# SensorBoard_v1.net
KiCad netlist of a schematic drawn in Altium Designer
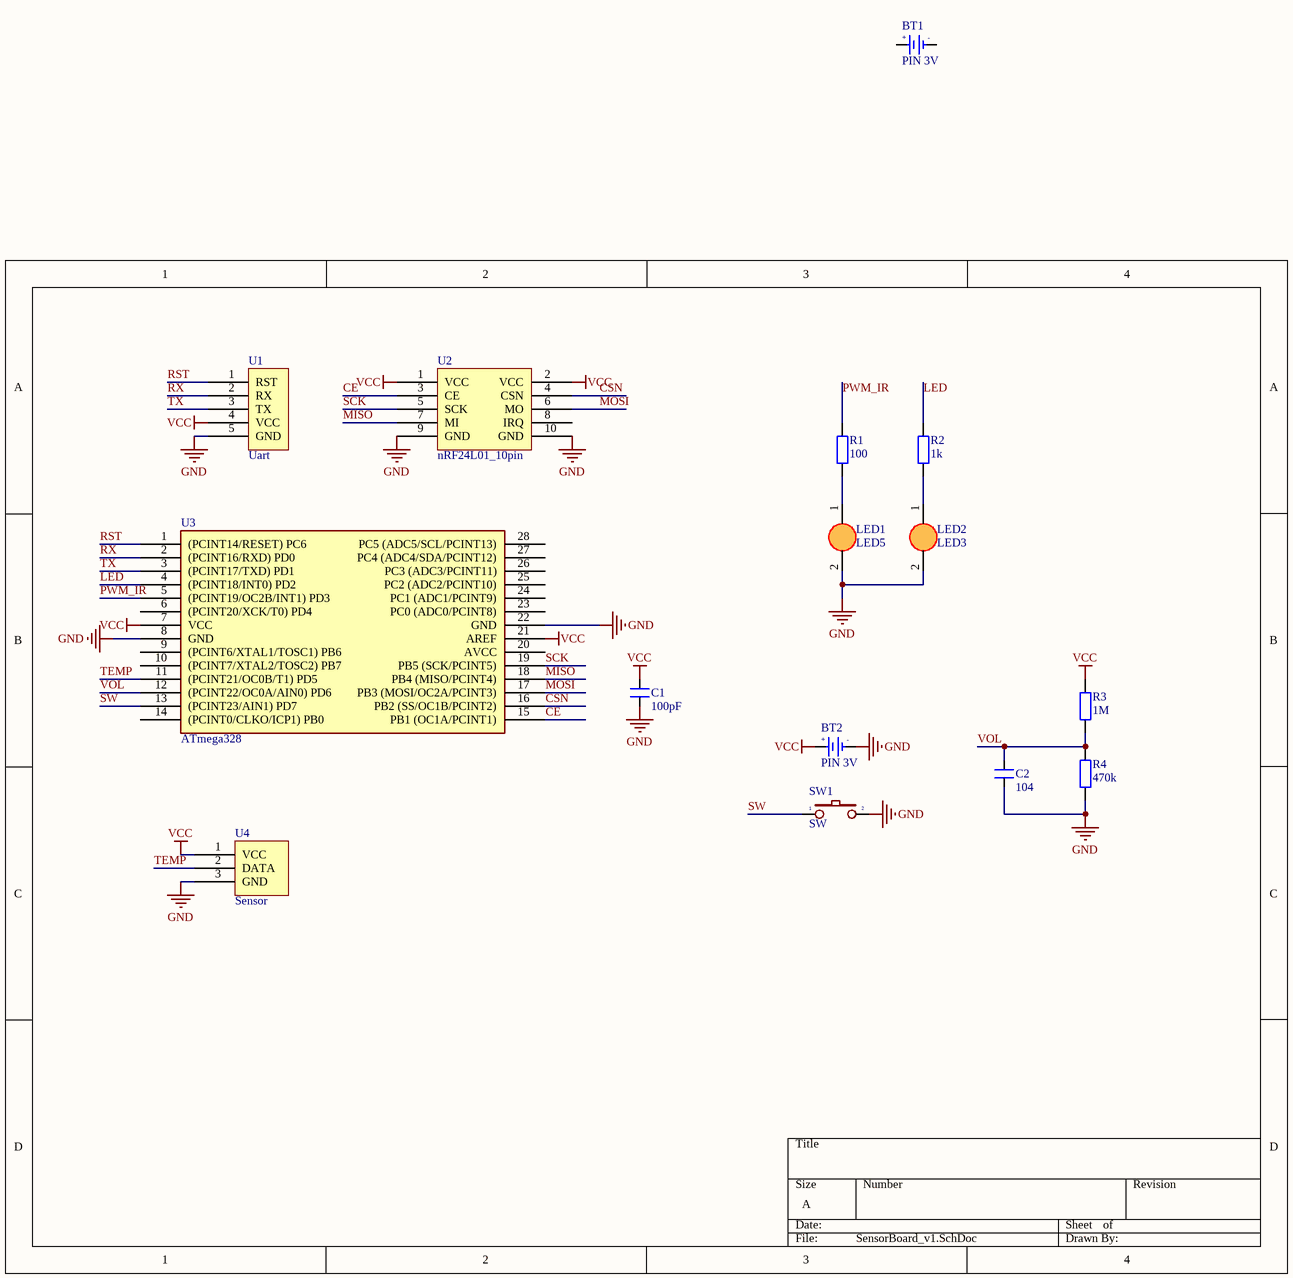
[diagram p0: SensorBoard_v1.SchDoc]

(export (version "E")
  (design (tool "Eeschema 10.0.6"))
  (components
    (comp (ref "BT1")
      (value "PIN 3V")
      (footprint "PIN3V")
      (description "Battery 3VDC")
      (libsource (lib "syhaunguyen") (part "PIN 3V"))
    )
    (comp (ref "BT2")
      (value "PIN 3V")
      (footprint "PIN3V")
      (description "Battery 3VDC")
      (libsource (lib "syhaunguyen") (part "PIN 3V"))
    )
    (comp (ref "C1")
      (value "100pF")
      (footprint "CN1")
      (description "Cap np  1pF - 472pF")
      (libsource (lib "syhaunguyen") (part "CN1"))
    )
    (comp (ref "C2")
      (value "104")
      (footprint "CN1.5")
      (description "Cap np 682pF => 104pF")
      (libsource (lib "syhaunguyen") (part "CN1.5"))
    )
    (comp (ref "LED1")
      (value "LED5")
      (footprint "LED5MM")
      (description "LED 5mm")
      (libsource (lib "myLibs") (part "LED 5mm"))
    )
    (comp (ref "LED2")
      (value "LED3")
      (footprint "LED3mm")
      (description "LED 3mm")
      (libsource (lib "myLibs") (part "LED 3mm"))
    )
    (comp (ref "R1")
      (value "100")
      (footprint "R1/4W")
      (description "Resistor 1/4W")
      (libsource (lib "myLibs") (part "R1/4W"))
    )
    (comp (ref "R2")
      (value "1k")
      (footprint "R1/4W")
      (description "Resistor 1/4W")
      (libsource (lib "myLibs") (part "R1/4W"))
    )
    (comp (ref "R3")
      (value "1M")
      (footprint "R1/4W")
      (description "Resistor 1/4W")
      (libsource (lib "myLibs") (part "R1/4W"))
    )
    (comp (ref "R4")
      (value "470k")
      (footprint "R1/4W")
      (description "Resistor 1/4W")
      (libsource (lib "myLibs") (part "R1/4W"))
    )
    (comp (ref "SW1")
      (value "SW")
      (footprint "SW2")
      (description "Switch button 2 pin")
      (libsource (lib "syhaunguyen") (part "SW2"))
    )
    (comp (ref "U1") (value "Uart") (footprint "CONG NAP") (libsource (lib "myLibs") (part "CONG NAP")))
    (comp (ref "U2")
      (value "nRF24L01_10pin")
      (footprint "NRF24L01_10PIN")
      (libsource (lib "myLibs") (part "nRF24L01_10pin"))
    )
    (comp (ref "U3") (value "ATmega328") (footprint "DIP28") (libsource (lib "myLibs") (part "ATmega328")))
    (comp (ref "U4")
      (value "Sensor")
      (footprint "TEMPSENSOR")
      (libsource (lib "myLibs") (part "Temp Sensor"))
    )
  )
  (nets
    (net (code "1") (name "/CE") (class "Default")
      (node (ref "U2") (pin "3") (pinfunction "CE_3") (pintype "passive"))
      (node (ref "U3") (pin "15") (pinfunction "PB1_(OC1A/PCINT1)_15") (pintype "passive"))
    )
    (net (code "2") (name "/CSN") (class "Default")
      (node (ref "U2") (pin "4") (pinfunction "CSN_4") (pintype "passive"))
      (node (ref "U3") (pin "16") (pinfunction "PB2_(SS/OC1B/PCINT2)_16") (pintype "passive"))
    )
    (net (code "3") (name "/LED") (class "Default")
      (node (ref "R2") (pin "1") (pinfunction "1_1") (pintype "passive"))
      (node (ref "U3") (pin "4") (pinfunction "(PCINT18/INT0)_PD2_4") (pintype "passive"))
    )
    (net (code "4") (name "/MISO") (class "Default")
      (node (ref "U2") (pin "7") (pinfunction "MI_7") (pintype "passive"))
      (node (ref "U3") (pin "18") (pinfunction "PB4_(MISO/PCINT4)_18") (pintype "passive"))
    )
    (net (code "5") (name "/MOSI") (class "Default")
      (node (ref "U2") (pin "6") (pinfunction "MO_6") (pintype "passive"))
      (node (ref "U3") (pin "17") (pinfunction "PB3_(MOSI/OC2A/PCINT3)_17") (pintype "passive"))
    )
    (net (code "6") (name "/PWM_IR") (class "Default")
      (node (ref "R1") (pin "2") (pinfunction "2_2") (pintype "passive"))
      (node (ref "U3") (pin "5") (pinfunction "(PCINT19/OC2B/INT1)_PD3_5") (pintype "passive"))
    )
    (net (code "7") (name "/RST") (class "Default")
      (node (ref "U1") (pin "1") (pinfunction "RST_1") (pintype "passive"))
      (node (ref "U3") (pin "1") (pinfunction "(PCINT14/RESET)_PC6_1") (pintype "passive"))
    )
    (net (code "8") (name "/RX") (class "Default")
      (node (ref "U1") (pin "2") (pinfunction "RX_2") (pintype "passive"))
      (node (ref "U3") (pin "2") (pinfunction "(PCINT16/RXD)_PD0_2") (pintype "passive"))
    )
    (net (code "9") (name "/SCK") (class "Default")
      (node (ref "U2") (pin "5") (pinfunction "SCK_5") (pintype "passive"))
      (node (ref "U3") (pin "19") (pinfunction "PB5_(SCK/PCINT5)_19") (pintype "passive"))
    )
    (net (code "10") (name "/SW") (class "Default")
      (node (ref "SW1") (pin "1") (pinfunction "1_1") (pintype "passive"))
      (node (ref "U3") (pin "13") (pinfunction "(PCINT23/AIN1)_PD7_13") (pintype "passive"))
    )
    (net (code "11") (name "/TEMP") (class "Default")
      (node (ref "U3") (pin "11") (pinfunction "(PCINT21/OC0B/T1)_PD5_11") (pintype "passive"))
      (node (ref "U4") (pin "2") (pinfunction "DATA_2") (pintype "passive"))
    )
    (net (code "12") (name "/TX") (class "Default")
      (node (ref "U1") (pin "3") (pinfunction "TX_3") (pintype "passive"))
      (node (ref "U3") (pin "3") (pinfunction "(PCINT17/TXD)_PD1_3") (pintype "passive"))
    )
    (net (code "13") (name "/VOL") (class "Default")
      (node (ref "C2") (pin "1") (pinfunction "1_1") (pintype "passive"))
      (node (ref "R3") (pin "2") (pinfunction "2_2") (pintype "passive"))
      (node (ref "R4") (pin "1") (pinfunction "1_1") (pintype "passive"))
      (node (ref "U3") (pin "12") (pinfunction "(PCINT22/OC0A/AIN0)_PD6_12") (pintype "passive"))
    )
    (net (code "14") (name "GND") (class "Default")
      (node (ref "BT2") (pin "2") (pinfunction "GND_2") (pintype "passive"))
      (node (ref "C1") (pin "2") (pinfunction "2_2") (pintype "passive"))
      (node (ref "C2") (pin "2") (pinfunction "2_2") (pintype "passive"))
      (node (ref "LED1") (pin "2") (pinfunction "K_2") (pintype "passive"))
      (node (ref "LED2") (pin "2") (pinfunction "K_2") (pintype "passive"))
      (node (ref "R4") (pin "2") (pinfunction "2_2") (pintype "passive"))
      (node (ref "SW1") (pin "2") (pinfunction "2_2") (pintype "passive"))
      (node (ref "U1") (pin "5") (pinfunction "GND_5") (pintype "passive"))
      (node (ref "U2") (pin "10") (pinfunction "GND_10") (pintype "passive"))
      (node (ref "U2") (pin "9") (pinfunction "GND_9") (pintype "passive"))
      (node (ref "U3") (pin "22") (pinfunction "GND_22") (pintype "passive"))
      (node (ref "U3") (pin "8") (pinfunction "GND_8") (pintype "passive"))
      (node (ref "U4") (pin "3") (pinfunction "GND_3") (pintype "passive"))
    )
    (net (code "15") (name "Net-(LED1-A)") (class "Default")
      (node (ref "LED1") (pin "1") (pinfunction "A_1") (pintype "passive"))
      (node (ref "R1") (pin "1") (pinfunction "1_1") (pintype "passive"))
    )
    (net (code "16") (name "Net-(LED2-A)") (class "Default")
      (node (ref "LED2") (pin "1") (pinfunction "A_1") (pintype "passive"))
      (node (ref "R2") (pin "2") (pinfunction "2_2") (pintype "passive"))
    )
    (net (code "17") (name "VCC") (class "Default")
      (node (ref "BT2") (pin "1") (pinfunction "+3V_1") (pintype "passive"))
      (node (ref "C1") (pin "1") (pinfunction "1_1") (pintype "passive"))
      (node (ref "R3") (pin "1") (pinfunction "1_1") (pintype "passive"))
      (node (ref "U1") (pin "4") (pinfunction "VCC_4") (pintype "passive"))
      (node (ref "U2") (pin "1") (pinfunction "VCC_1") (pintype "passive"))
      (node (ref "U2") (pin "2") (pinfunction "VCC_2") (pintype "passive"))
      (node (ref "U3") (pin "21") (pinfunction "AREF_21") (pintype "passive"))
      (node (ref "U3") (pin "7") (pinfunction "VCC_7") (pintype "passive"))
      (node (ref "U4") (pin "1") (pinfunction "VCC_1") (pintype "passive"))
    )
    (net (code "18") (name "unconnected-(BT1-+3V-Pad1)") (class "Default")
      (node (ref "BT1") (pin "1") (pinfunction "+3V_1") (pintype "passive"))
    )
    (net (code "19") (name "unconnected-(BT1-GND-Pad2)") (class "Default")
      (node (ref "BT1") (pin "2") (pinfunction "GND_2") (pintype "passive"))
    )
    (net (code "20") (name "unconnected-(U2-IRQ-Pad8)") (class "Default")
      (node (ref "U2") (pin "8") (pinfunction "IRQ_8") (pintype "passive"))
    )
    (net (code "21") (name "unconnected-(U3-(PCINT0{slash}CLKO{slash}ICP1)_PB0-Pad14)") (class "Default")
      (node (ref "U3") (pin "14") (pinfunction "(PCINT0/CLKO/ICP1)_PB0_14") (pintype "passive"))
    )
    (net (code "22") (name "unconnected-(U3-(PCINT6{slash}XTAL1{slash}TOSC1)_PB6-Pad9)") (class "Default")
      (node (ref "U3") (pin "9") (pinfunction "(PCINT6/XTAL1/TOSC1)_PB6_9") (pintype "passive"))
    )
    (net (code "23") (name "unconnected-(U3-(PCINT7{slash}XTAL2{slash}TOSC2)_PB7-Pad10)") (class "Default")
      (node (ref "U3") (pin "10") (pinfunction "(PCINT7/XTAL2/TOSC2)_PB7_10") (pintype "passive"))
    )
    (net (code "24") (name "unconnected-(U3-(PCINT20{slash}XCK{slash}T0)_PD4-Pad6)") (class "Default")
      (node (ref "U3") (pin "6") (pinfunction "(PCINT20/XCK/T0)_PD4_6") (pintype "passive"))
    )
    (net (code "25") (name "unconnected-(U3-AVCC-Pad20)") (class "Default")
      (node (ref "U3") (pin "20") (pinfunction "AVCC_20") (pintype "passive"))
    )
    (net (code "26") (name "unconnected-(U3-PC0_(ADC0{slash}PCINT8)-Pad23)") (class "Default")
      (node (ref "U3") (pin "23") (pinfunction "PC0_(ADC0/PCINT8)_23") (pintype "passive"))
    )
    (net (code "27") (name "unconnected-(U3-PC1_(ADC1{slash}PCINT9)-Pad24)") (class "Default")
      (node (ref "U3") (pin "24") (pinfunction "PC1_(ADC1/PCINT9)_24") (pintype "passive"))
    )
    (net (code "28") (name "unconnected-(U3-PC2_(ADC2{slash}PCINT10)-Pad25)") (class "Default")
      (node (ref "U3") (pin "25") (pinfunction "PC2_(ADC2/PCINT10)_25") (pintype "passive"))
    )
    (net (code "29") (name "unconnected-(U3-PC3_(ADC3{slash}PCINT11)-Pad26)") (class "Default")
      (node (ref "U3") (pin "26") (pinfunction "PC3_(ADC3/PCINT11)_26") (pintype "passive"))
    )
    (net (code "30") (name "unconnected-(U3-PC4_(ADC4{slash}SDA{slash}PCINT12)-Pad27)") (class "Default")
      (node (ref "U3") (pin "27") (pinfunction "PC4_(ADC4/SDA/PCINT12)_27") (pintype "passive"))
    )
    (net (code "31") (name "unconnected-(U3-PC5_(ADC5{slash}SCL{slash}PCINT13)-Pad28)") (class "Default")
      (node (ref "U3") (pin "28") (pinfunction "PC5_(ADC5/SCL/PCINT13)_28") (pintype "passive"))
    )
  )
)
